# RAMConnection.net
KiCad netlist of a schematic drawn in Altium Designer
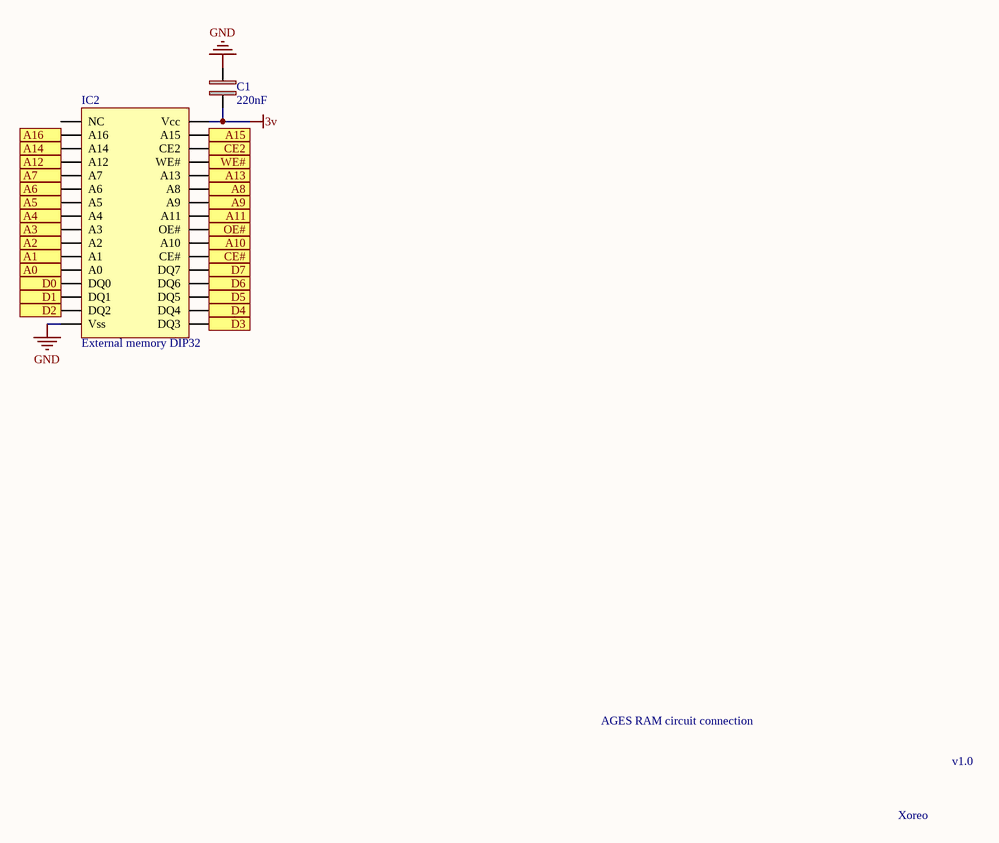
[diagram p0: RAMConnection.SchDoc]

(export (version "E")
  (design (tool "Eeschema 10.0.6"))
  (components
    (comp (ref "C1")
      (value "220nF")
      (footprint "C0805C224K5RACTU")
      (description "0805 C 220nF Ceramic Multilayer Capacitor; 50 VDC; +125degC; X7R Dielec; +/-10%")
      (fields
        (field (name "MANUFACTURER") "KEMET")
        (field (name "MANUFACTURER PART NUMBER") "C0805C224K5RACTU")
      )
      (libsource (lib "Mobo") (part "Capacitor{colon} 0.22µF"))
    )
    (comp (ref "IC2")
      (value "External memory DIP32")
      (footprint "DIP32 HDR")
      (description "AS6C1008 Series 1-Mbit (128 K x 8) 3 V 55 ns CMOS Static RAM - PDIP-32")
      (fields
        (field (name "MANUFACTURER") "Alliance Memory")
        (field (name "MANUFACTURER PART NUMBER") "AS6C1008-55PCN")
      )
      (libsource (lib "Mobo") (part "IC{colon} AS6C1008"))
    )
  )
  (nets
    (net (code "1") (name "/A0") (class "Default")
      (node (ref "IC2") (pin "12") (pinfunction "A0_12") (pintype "passive"))
    )
    (net (code "2") (name "/A1") (class "Default")
      (node (ref "IC2") (pin "11") (pinfunction "A1_11") (pintype "passive"))
    )
    (net (code "3") (name "/A2") (class "Default")
      (node (ref "IC2") (pin "10") (pinfunction "A2_10") (pintype "passive"))
    )
    (net (code "4") (name "/A3") (class "Default")
      (node (ref "IC2") (pin "9") (pinfunction "A3_9") (pintype "passive"))
    )
    (net (code "5") (name "/A4") (class "Default")
      (node (ref "IC2") (pin "8") (pinfunction "A4_8") (pintype "passive"))
    )
    (net (code "6") (name "/A5") (class "Default")
      (node (ref "IC2") (pin "7") (pinfunction "A5_7") (pintype "passive"))
    )
    (net (code "7") (name "/A6") (class "Default")
      (node (ref "IC2") (pin "6") (pinfunction "A6_6") (pintype "passive"))
    )
    (net (code "8") (name "/A7") (class "Default")
      (node (ref "IC2") (pin "5") (pinfunction "A7_5") (pintype "passive"))
    )
    (net (code "9") (name "/A8") (class "Default")
      (node (ref "IC2") (pin "27") (pinfunction "A8_27") (pintype "passive"))
    )
    (net (code "10") (name "/A9") (class "Default")
      (node (ref "IC2") (pin "26") (pinfunction "A9_26") (pintype "passive"))
    )
    (net (code "11") (name "/A10") (class "Default")
      (node (ref "IC2") (pin "23") (pinfunction "A10_23") (pintype "passive"))
    )
    (net (code "12") (name "/A11") (class "Default")
      (node (ref "IC2") (pin "25") (pinfunction "A11_25") (pintype "passive"))
    )
    (net (code "13") (name "/A12") (class "Default")
      (node (ref "IC2") (pin "4") (pinfunction "A12_4") (pintype "passive"))
    )
    (net (code "14") (name "/A13") (class "Default")
      (node (ref "IC2") (pin "28") (pinfunction "A13_28") (pintype "passive"))
    )
    (net (code "15") (name "/A14") (class "Default")
      (node (ref "IC2") (pin "3") (pinfunction "A14_3") (pintype "passive"))
    )
    (net (code "16") (name "/A15") (class "Default")
      (node (ref "IC2") (pin "31") (pinfunction "A15_31") (pintype "passive"))
    )
    (net (code "17") (name "/A16") (class "Default")
      (node (ref "IC2") (pin "2") (pinfunction "A16_2") (pintype "passive"))
    )
    (net (code "18") (name "/CE#") (class "Default")
      (node (ref "IC2") (pin "22") (pinfunction "CE#_22") (pintype "passive"))
    )
    (net (code "19") (name "/CE2") (class "Default")
      (node (ref "IC2") (pin "30") (pinfunction "CE2_30") (pintype "passive"))
    )
    (net (code "20") (name "/D0") (class "Default")
      (node (ref "IC2") (pin "13") (pinfunction "DQ0_13") (pintype "passive"))
    )
    (net (code "21") (name "/D1") (class "Default")
      (node (ref "IC2") (pin "14") (pinfunction "DQ1_14") (pintype "passive"))
    )
    (net (code "22") (name "/D2") (class "Default")
      (node (ref "IC2") (pin "15") (pinfunction "DQ2_15") (pintype "passive"))
    )
    (net (code "23") (name "/D3") (class "Default")
      (node (ref "IC2") (pin "17") (pinfunction "DQ3_17") (pintype "passive"))
    )
    (net (code "24") (name "/D4") (class "Default")
      (node (ref "IC2") (pin "18") (pinfunction "DQ4_18") (pintype "passive"))
    )
    (net (code "25") (name "/D5") (class "Default")
      (node (ref "IC2") (pin "19") (pinfunction "DQ5_19") (pintype "passive"))
    )
    (net (code "26") (name "/D6") (class "Default")
      (node (ref "IC2") (pin "20") (pinfunction "DQ6_20") (pintype "passive"))
    )
    (net (code "27") (name "/D7") (class "Default")
      (node (ref "IC2") (pin "21") (pinfunction "DQ7_21") (pintype "passive"))
    )
    (net (code "28") (name "/OE#") (class "Default")
      (node (ref "IC2") (pin "24") (pinfunction "OE#_24") (pintype "passive"))
    )
    (net (code "29") (name "/WE#") (class "Default")
      (node (ref "IC2") (pin "29") (pinfunction "WE#_29") (pintype "passive"))
    )
    (net (code "30") (name "3v") (class "Default")
      (node (ref "C1") (pin "2") (pinfunction "2_2") (pintype "passive"))
      (node (ref "IC2") (pin "32") (pinfunction "Vcc_32") (pintype "passive"))
    )
    (net (code "31") (name "GND") (class "Default")
      (node (ref "C1") (pin "1") (pinfunction "1_1") (pintype "passive"))
      (node (ref "IC2") (pin "16") (pinfunction "Vss_16") (pintype "passive"))
    )
    (net (code "32") (name "unconnected-(IC2-NC-Pad1)") (class "Default")
      (node (ref "IC2") (pin "1") (pinfunction "NC_1") (pintype "passive"))
    )
  )
)
